# Tractive_System_Active_Light_rev1.net
KiCad netlist of a schematic drawn in EAGLE
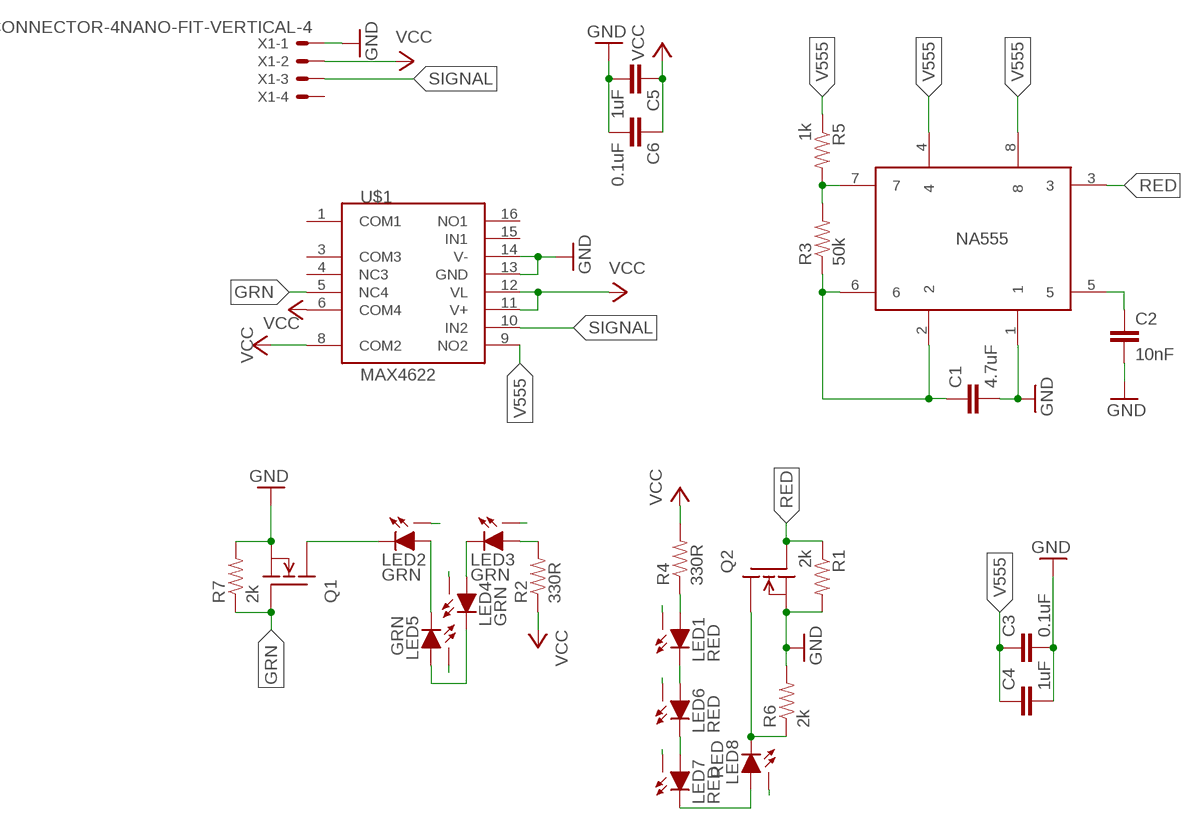
[diagram p0: schematic, sheet 1]

(export (version "E")
  (design (tool "Eeschema 10.0.6"))
  (components
    (comp (ref "C1")
      (value "4.7uF")
      (footprint "eagle-import:0603-CAP")
      (fields (field (name "TOLERANCE") "5%") (field (name "VOLTAGE") "25V"))
      (libsource (lib "eagle-import") (part "CAP0603-CAP"))
    )
    (comp (ref "C2")
      (value "10nF")
      (footprint "eagle-import:0603-CAP")
      (fields (field (name "TOLERANCE") "5%") (field (name "VOLTAGE") "25V"))
      (libsource (lib "eagle-import") (part "CAP0603-CAP"))
    )
    (comp (ref "C3")
      (value "0.1uF")
      (footprint "eagle-import:0603-CAP")
      (fields (field (name "TOLERANCE") "5%") (field (name "VOLTAGE") "25V"))
      (libsource (lib "eagle-import") (part "CAP0603-CAP"))
    )
    (comp (ref "C4")
      (value "1uF")
      (footprint "eagle-import:0603-CAP")
      (fields (field (name "TOLERANCE") "5%") (field (name "VOLTAGE") "25V"))
      (libsource (lib "eagle-import") (part "CAP0603-CAP"))
    )
    (comp (ref "C5")
      (value "1uF")
      (footprint "eagle-import:0603-CAP")
      (fields (field (name "TOLERANCE") "5%") (field (name "VOLTAGE") "25V"))
      (libsource (lib "eagle-import") (part "CAP0603-CAP"))
    )
    (comp (ref "C6")
      (value "0.1uF")
      (footprint "eagle-import:0603-CAP")
      (fields (field (name "TOLERANCE") "5%") (field (name "VOLTAGE") "25V"))
      (libsource (lib "eagle-import") (part "CAP0603-CAP"))
    )
    (comp (ref "LED1")
      (value "RED")
      (footprint "eagle-import:XP-E2")
      (libsource (lib "eagle-import") (part "XP-E2XP-E2"))
    )
    (comp (ref "LED2")
      (value "GRN")
      (footprint "eagle-import:XP-E2")
      (libsource (lib "eagle-import") (part "XP-E2XP-E2"))
    )
    (comp (ref "LED3")
      (value "GRN")
      (footprint "eagle-import:XP-E2")
      (libsource (lib "eagle-import") (part "XP-E2XP-E2"))
    )
    (comp (ref "LED4")
      (value "GRN")
      (footprint "eagle-import:XP-E2")
      (libsource (lib "eagle-import") (part "XP-E2XP-E2"))
    )
    (comp (ref "LED5")
      (value "GRN")
      (footprint "eagle-import:XP-E2")
      (libsource (lib "eagle-import") (part "XP-E2XP-E2"))
    )
    (comp (ref "LED6")
      (value "RED")
      (footprint "eagle-import:XP-E2")
      (libsource (lib "eagle-import") (part "XP-E2XP-E2"))
    )
    (comp (ref "LED7")
      (value "RED")
      (footprint "eagle-import:XP-E2")
      (libsource (lib "eagle-import") (part "XP-E2XP-E2"))
    )
    (comp (ref "LED8")
      (value "RED")
      (footprint "eagle-import:XP-E2")
      (libsource (lib "eagle-import") (part "XP-E2XP-E2"))
    )
    (comp (ref "NA555")
      (value "NA555SO-8")
      (footprint "eagle-import:SOIC-08")
      (libsource (lib "eagle-import") (part "NA555SO-8"))
    )
    (comp (ref "Q1")
      (value "DMG3406LSOT")
      (footprint "eagle-import:SOT23")
      (libsource (lib "eagle-import") (part "DMG3406LSOT"))
    )
    (comp (ref "Q2")
      (value "DMG3406LSOT")
      (footprint "eagle-import:SOT23")
      (libsource (lib "eagle-import") (part "DMG3406LSOT"))
    )
    (comp (ref "R1")
      (value "2k")
      (footprint "eagle-import:0603-RES")
      (fields (field (name "TOLERANCE") "1%"))
      (libsource (lib "eagle-import") (part "RESISTOR0603-RES"))
    )
    (comp (ref "R2")
      (value "330R")
      (footprint "eagle-import:0603-RES")
      (fields (field (name "TOLERANCE") "1%"))
      (libsource (lib "eagle-import") (part "RESISTOR0603-RES"))
    )
    (comp (ref "R3")
      (value "50k")
      (footprint "eagle-import:0603-RES")
      (fields (field (name "TOLERANCE") "1%"))
      (libsource (lib "eagle-import") (part "RESISTOR0603-RES"))
    )
    (comp (ref "R4")
      (value "330R")
      (footprint "eagle-import:0603-RES")
      (fields (field (name "TOLERANCE") "1%"))
      (libsource (lib "eagle-import") (part "RESISTOR0603-RES"))
    )
    (comp (ref "R5")
      (value "1k")
      (footprint "eagle-import:0603-RES")
      (fields (field (name "TOLERANCE") "1%"))
      (libsource (lib "eagle-import") (part "RESISTOR0603-RES"))
    )
    (comp (ref "R6")
      (value "2k")
      (footprint "eagle-import:0603-RES")
      (fields (field (name "TOLERANCE") "1%"))
      (libsource (lib "eagle-import") (part "RESISTOR0603-RES"))
    )
    (comp (ref "R7")
      (value "2k")
      (footprint "eagle-import:0603-RES")
      (fields (field (name "TOLERANCE") "1%"))
      (libsource (lib "eagle-import") (part "RESISTOR0603-RES"))
    )
    (comp (ref "U$1")
      (value "MAX4622")
      (footprint "eagle-import:SO16")
      (libsource (lib "eagle-import") (part "MAX4622"))
    )
    (comp (ref "X1")
      (value "CONNECTOR-4NANO-FIT-VERTICAL-4")
      (footprint "eagle-import:NANO-FIT_VERTICAL-4")
      (libsource (lib "eagle-import") (part "CONNECTOR-4NANO-FIT-VERTICAL-4"))
    )
  )
  (nets
    (net (code "1") (name "GND") (class "Default")
      (node (ref "C1") (pin "2") (pinfunction "2_2") (pintype "passive"))
      (node (ref "C2") (pin "2") (pinfunction "2_2") (pintype "passive"))
      (node (ref "C3") (pin "2") (pinfunction "2_2") (pintype "passive"))
      (node (ref "C4") (pin "2") (pinfunction "2_2") (pintype "passive"))
      (node (ref "C5") (pin "2") (pinfunction "2_2") (pintype "passive"))
      (node (ref "C6") (pin "2") (pinfunction "2_2") (pintype "passive"))
      (node (ref "NA555") (pin "1") (pinfunction "1_1") (pintype "bidirectional"))
      (node (ref "Q1") (pin "2") (pinfunction "S_2") (pintype "passive"))
      (node (ref "Q2") (pin "2") (pinfunction "S_2") (pintype "passive"))
      (node (ref "R1") (pin "2") (pinfunction "2_2") (pintype "passive"))
      (node (ref "R6") (pin "2") (pinfunction "2_2") (pintype "passive"))
      (node (ref "R7") (pin "2") (pinfunction "2_2") (pintype "passive"))
      (node (ref "U$1") (pin "13") (pinfunction "GND_13") (pintype "bidirectional"))
      (node (ref "U$1") (pin "14") (pinfunction "V-_14") (pintype "bidirectional"))
      (node (ref "X1") (pin "P$1") (pinfunction "S_P$1") (pintype "passive"))
    )
    (net (code "2") (name "GRN") (class "Default")
      (node (ref "Q1") (pin "1") (pinfunction "G_1") (pintype "passive"))
      (node (ref "R7") (pin "1") (pinfunction "1_1") (pintype "passive"))
      (node (ref "U$1") (pin "5") (pinfunction "NC4_5") (pintype "bidirectional"))
    )
    (net (code "3") (name "Net-(C1-Pad1)") (class "Default")
      (node (ref "C1") (pin "1") (pinfunction "1_1") (pintype "passive"))
      (node (ref "NA555") (pin "2") (pinfunction "2_2") (pintype "bidirectional"))
      (node (ref "NA555") (pin "6") (pinfunction "6_6") (pintype "bidirectional"))
      (node (ref "R3") (pin "1") (pinfunction "1_1") (pintype "passive"))
    )
    (net (code "4") (name "Net-(C2-Pad1)") (class "Default")
      (node (ref "C2") (pin "1") (pinfunction "1_1") (pintype "passive"))
      (node (ref "NA555") (pin "5") (pinfunction "5_5") (pintype "bidirectional"))
    )
    (net (code "5") (name "Net-(LED1-PadA)") (class "Default")
      (node (ref "LED1") (pin "A") (pinfunction "A_A") (pintype "passive"))
      (node (ref "R4") (pin "1") (pinfunction "1_1") (pintype "passive"))
    )
    (net (code "6") (name "Net-(LED1-PadC)") (class "Default")
      (node (ref "LED1") (pin "C") (pinfunction "C_C") (pintype "passive"))
      (node (ref "LED6") (pin "A") (pinfunction "A_A") (pintype "passive"))
    )
    (net (code "7") (name "Net-(LED2-PadA)") (class "Default")
      (node (ref "LED2") (pin "A") (pinfunction "A_A") (pintype "passive"))
      (node (ref "LED5") (pin "C") (pinfunction "C_C") (pintype "passive"))
    )
    (net (code "8") (name "Net-(LED3-PadA)") (class "Default")
      (node (ref "LED3") (pin "A") (pinfunction "A_A") (pintype "passive"))
      (node (ref "R2") (pin "2") (pinfunction "2_2") (pintype "passive"))
    )
    (net (code "9") (name "Net-(LED3-PadC)") (class "Default")
      (node (ref "LED3") (pin "C") (pinfunction "C_C") (pintype "passive"))
      (node (ref "LED4") (pin "A") (pinfunction "A_A") (pintype "passive"))
    )
    (net (code "10") (name "Net-(LED4-PadC)") (class "Default")
      (node (ref "LED4") (pin "C") (pinfunction "C_C") (pintype "passive"))
      (node (ref "LED5") (pin "A") (pinfunction "A_A") (pintype "passive"))
    )
    (net (code "11") (name "Net-(LED6-PadC)") (class "Default")
      (node (ref "LED6") (pin "C") (pinfunction "C_C") (pintype "passive"))
      (node (ref "LED7") (pin "A") (pinfunction "A_A") (pintype "passive"))
    )
    (net (code "12") (name "Net-(LED7-PadC)") (class "Default")
      (node (ref "LED7") (pin "C") (pinfunction "C_C") (pintype "passive"))
      (node (ref "LED8") (pin "A") (pinfunction "A_A") (pintype "passive"))
    )
    (net (code "13") (name "Net-(NA555-Pad7)") (class "Default")
      (node (ref "NA555") (pin "7") (pinfunction "7_7") (pintype "bidirectional"))
      (node (ref "R3") (pin "2") (pinfunction "2_2") (pintype "passive"))
      (node (ref "R5") (pin "2") (pinfunction "2_2") (pintype "passive"))
    )
    (net (code "14") (name "Net-(Q1-D)") (class "Default")
      (node (ref "LED2") (pin "C") (pinfunction "C_C") (pintype "passive"))
      (node (ref "Q1") (pin "3") (pinfunction "D_3") (pintype "passive"))
    )
    (net (code "15") (name "Net-(Q2-D)") (class "Default")
      (node (ref "LED8") (pin "C") (pinfunction "C_C") (pintype "passive"))
      (node (ref "Q2") (pin "3") (pinfunction "D_3") (pintype "passive"))
      (node (ref "R6") (pin "1") (pinfunction "1_1") (pintype "passive"))
    )
    (net (code "16") (name "RED") (class "Default")
      (node (ref "NA555") (pin "3") (pinfunction "3_3") (pintype "bidirectional"))
      (node (ref "Q2") (pin "1") (pinfunction "G_1") (pintype "passive"))
      (node (ref "R1") (pin "1") (pinfunction "1_1") (pintype "passive"))
    )
    (net (code "17") (name "SIGNAL") (class "Default")
      (node (ref "U$1") (pin "10") (pinfunction "IN2_10") (pintype "bidirectional"))
      (node (ref "X1") (pin "P$3") (pinfunction "S_P$3") (pintype "passive"))
    )
    (net (code "18") (name "V555") (class "Default")
      (node (ref "C3") (pin "1") (pinfunction "1_1") (pintype "passive"))
      (node (ref "C4") (pin "1") (pinfunction "1_1") (pintype "passive"))
      (node (ref "NA555") (pin "4") (pinfunction "4_4") (pintype "bidirectional"))
      (node (ref "NA555") (pin "8") (pinfunction "8_8") (pintype "bidirectional"))
      (node (ref "R5") (pin "1") (pinfunction "1_1") (pintype "passive"))
      (node (ref "U$1") (pin "9") (pinfunction "NO2_9") (pintype "bidirectional"))
    )
    (net (code "19") (name "VCC") (class "Default")
      (node (ref "C5") (pin "1") (pinfunction "1_1") (pintype "passive"))
      (node (ref "C6") (pin "1") (pinfunction "1_1") (pintype "passive"))
      (node (ref "R2") (pin "1") (pinfunction "1_1") (pintype "passive"))
      (node (ref "R4") (pin "2") (pinfunction "2_2") (pintype "passive"))
      (node (ref "U$1") (pin "11") (pinfunction "V+_11") (pintype "bidirectional"))
      (node (ref "U$1") (pin "12") (pinfunction "VL_12") (pintype "bidirectional"))
      (node (ref "U$1") (pin "6") (pinfunction "COM4_6") (pintype "bidirectional"))
      (node (ref "U$1") (pin "8") (pinfunction "COM2_8") (pintype "bidirectional"))
      (node (ref "X1") (pin "P$2") (pinfunction "S_P$2") (pintype "passive"))
    )
    (net (code "20") (name "unconnected-(LED1-PadX)") (class "Default")
      (node (ref "LED1") (pin "X") (pinfunction "X_X") (pintype "passive"))
    )
    (net (code "21") (name "unconnected-(LED2-PadX)") (class "Default")
      (node (ref "LED2") (pin "X") (pinfunction "X_X") (pintype "passive"))
    )
    (net (code "22") (name "unconnected-(LED3-PadX)") (class "Default")
      (node (ref "LED3") (pin "X") (pinfunction "X_X") (pintype "passive"))
    )
    (net (code "23") (name "unconnected-(LED4-PadX)") (class "Default")
      (node (ref "LED4") (pin "X") (pinfunction "X_X") (pintype "passive"))
    )
    (net (code "24") (name "unconnected-(LED5-PadX)") (class "Default")
      (node (ref "LED5") (pin "X") (pinfunction "X_X") (pintype "passive"))
    )
    (net (code "25") (name "unconnected-(LED6-PadX)") (class "Default")
      (node (ref "LED6") (pin "X") (pinfunction "X_X") (pintype "passive"))
    )
    (net (code "26") (name "unconnected-(LED7-PadX)") (class "Default")
      (node (ref "LED7") (pin "X") (pinfunction "X_X") (pintype "passive"))
    )
    (net (code "27") (name "unconnected-(LED8-PadX)") (class "Default")
      (node (ref "LED8") (pin "X") (pinfunction "X_X") (pintype "passive"))
    )
    (net (code "28") (name "unconnected-(U$1-COM1-Pad1)") (class "Default")
      (node (ref "U$1") (pin "1") (pinfunction "COM1_1") (pintype "bidirectional"))
    )
    (net (code "29") (name "unconnected-(U$1-COM3-Pad3)") (class "Default")
      (node (ref "U$1") (pin "3") (pinfunction "COM3_3") (pintype "bidirectional"))
    )
    (net (code "30") (name "unconnected-(U$1-IN1-Pad15)") (class "Default")
      (node (ref "U$1") (pin "15") (pinfunction "IN1_15") (pintype "bidirectional"))
    )
    (net (code "31") (name "unconnected-(U$1-NC3-Pad4)") (class "Default")
      (node (ref "U$1") (pin "4") (pinfunction "NC3_4") (pintype "bidirectional"))
    )
    (net (code "32") (name "unconnected-(U$1-NO1-Pad16)") (class "Default")
      (node (ref "U$1") (pin "16") (pinfunction "NO1_16") (pintype "bidirectional"))
    )
    (net (code "33") (name "unconnected-(X1D-S-PadP$4)") (class "Default")
      (node (ref "X1") (pin "P$4") (pinfunction "S_P$4") (pintype "passive"))
    )
  )
)
